# power_phase.net
KiCad netlist of a schematic drawn in Altium Designer
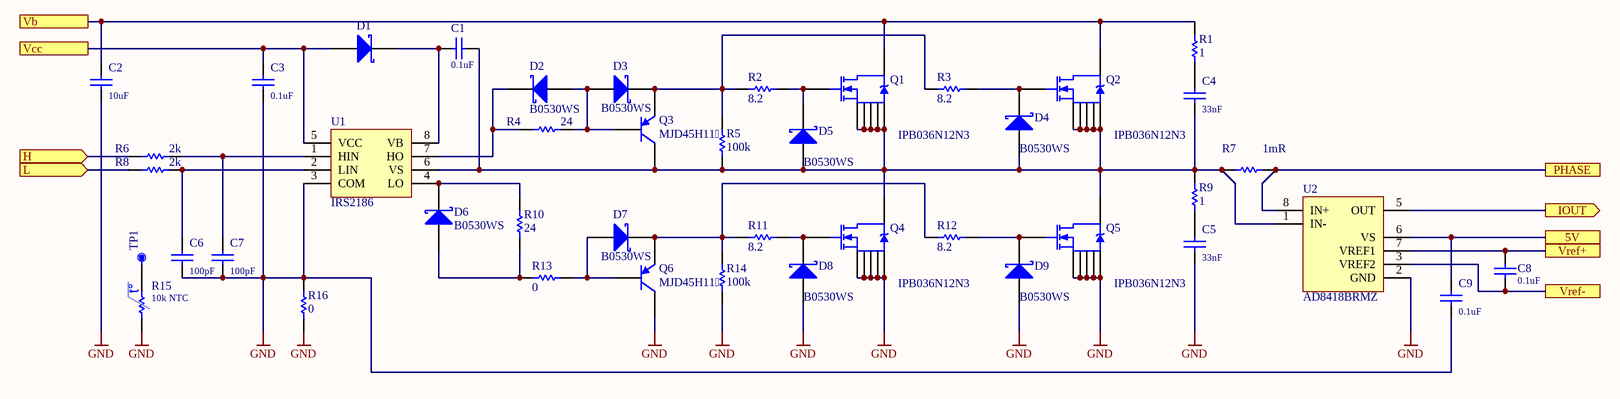
[diagram p0: power_phase.schdoc]

(export (version "E")
  (design (tool "Eeschema 10.0.6"))
  (components
    (comp (ref "C1")
      (value "0.1uF")
      (footprint "C0805_L")
      (description "0.1uF 50V 0603")
      (libsource (lib "Miscellaneous Devices") (part "CAP"))
    )
    (comp (ref "C2")
      (value "10uF")
      (footprint "C2220")
      (description "10uF 100V 2220")
      (libsource (lib "Miscellaneous Devices") (part "CAP"))
    )
    (comp (ref "C3")
      (value "0.1uF")
      (footprint "C0603")
      (description "0.1uF 50V 0603")
      (libsource (lib "Miscellaneous Devices") (part "CAP"))
    )
    (comp (ref "C4")
      (value "33nF")
      (footprint "C0805")
      (description "33nF 100V 1206")
      (libsource (lib "Miscellaneous Devices") (part "CAP"))
    )
    (comp (ref "C5")
      (value "33nF")
      (footprint "C0805")
      (description "33nF 100V 1206")
      (libsource (lib "Miscellaneous Devices") (part "CAP"))
    )
    (comp (ref "C6")
      (value "100pF")
      (footprint "C0402")
      (description "100pF 50V 0402")
      (libsource (lib "Miscellaneous Devices") (part "CAP"))
    )
    (comp (ref "C7")
      (value "100pF")
      (footprint "C0402")
      (description "100pF 50V 0402")
      (libsource (lib "Miscellaneous Devices") (part "CAP"))
    )
    (comp (ref "C8")
      (value "0.1uF")
      (footprint "C0402")
      (description "0.1uF 50V 0603")
      (libsource (lib "Miscellaneous Devices") (part "CAP"))
    )
    (comp (ref "C9")
      (value "0.1uF")
      (footprint "C0402")
      (description "0.1uF 50V 0603")
      (libsource (lib "Miscellaneous Devices") (part "CAP"))
    )
    (comp (ref "D1")
      (value "~")
      (footprint "SOD-323")
      (description "100V SOD-323")
      (libsource (lib "Miscellaneous Devices") (part "Diode 10TQ035_1"))
    )
    (comp (ref "D2")
      (value "B0530WS")
      (footprint "SOD-323")
      (description "Schottky 0.5A 30V SOD-323")
      (libsource (lib "Miscellaneous Devices") (part "Diode 10TQ035_1"))
    )
    (comp (ref "D3")
      (value "B0530WS")
      (footprint "SOD-323")
      (description "Schottky 0.5A 30V SOD-323")
      (libsource (lib "Miscellaneous Devices") (part "Diode 10TQ035_1"))
    )
    (comp (ref "D4")
      (value "B0530WS")
      (footprint "SOD-323")
      (description "Schottky 0.5A 30V SOD-323")
      (libsource (lib "Miscellaneous Devices") (part "Diode 10TQ035_1"))
    )
    (comp (ref "D5")
      (value "B0530WS")
      (footprint "SOD-323")
      (description "Schottky 0.5A 30V SOD-323")
      (libsource (lib "Miscellaneous Devices") (part "Diode 10TQ035_1"))
    )
    (comp (ref "D6")
      (value "B0530WS")
      (footprint "SOD-323")
      (description "Schottky 0.5A 30V SOD-323")
      (libsource (lib "Miscellaneous Devices") (part "Diode 10TQ035_1"))
    )
    (comp (ref "D7")
      (value "B0530WS")
      (footprint "SOD-323")
      (description "Schottky 0.5A 30V SOD-323")
      (libsource (lib "Miscellaneous Devices") (part "Diode 10TQ035_1"))
    )
    (comp (ref "D8")
      (value "B0530WS")
      (footprint "SOD-323")
      (description "Schottky 0.5A 30V SOD-323")
      (libsource (lib "Miscellaneous Devices") (part "Diode 10TQ035_1"))
    )
    (comp (ref "D9")
      (value "B0530WS")
      (footprint "SOD-323")
      (description "Schottky 0.5A 30V SOD-323")
      (libsource (lib "Miscellaneous Devices") (part "Diode 10TQ035_1"))
    )
    (comp (ref "Q1")
      (value "IPB036N12N3")
      (footprint "TO-263-7")
      (description "IPB036N12N3GATMA1")
      (libsource (lib "Miscellaneous Devices") (part "NMOS-2"))
    )
    (comp (ref "Q2")
      (value "IPB036N12N3")
      (footprint "TO-263-7")
      (description "IPB036N12N3GATMA1")
      (libsource (lib "Miscellaneous Devices") (part "NMOS-2"))
    )
    (comp (ref "Q3")
      (value "MJD45H11")
      (footprint "TO-252AA")
      (description "PNP Bipolar Transistor")
      (libsource (lib "Miscellaneous Devices") (part "PNP"))
    )
    (comp (ref "Q4")
      (value "IPB036N12N3")
      (footprint "TO-263-7")
      (description "IPB036N12N3GATMA1")
      (libsource (lib "Miscellaneous Devices") (part "NMOS-2"))
    )
    (comp (ref "Q5")
      (value "IPB036N12N3")
      (footprint "TO-263-7")
      (description "IPB036N12N3GATMA1")
      (libsource (lib "Miscellaneous Devices") (part "NMOS-2"))
    )
    (comp (ref "Q6")
      (value "MJD45H11")
      (footprint "TO-252AA")
      (description "PNP Bipolar Transistor")
      (libsource (lib "Miscellaneous Devices") (part "PNP"))
    )
    (comp (ref "R1")
      (value "1")
      (footprint "R1206")
      (description "1R 5% 1206")
      (libsource (lib "Miscellaneous Devices") (part "Res1"))
    )
    (comp (ref "R2")
      (value "8.2")
      (footprint "R0805")
      (description "8.2R 5% 0805")
      (libsource (lib "Miscellaneous Devices") (part "Res1"))
    )
    (comp (ref "R3")
      (value "8.2")
      (footprint "R0805")
      (description "8.2R 5% 0805")
      (libsource (lib "Miscellaneous Devices") (part "Res1"))
    )
    (comp (ref "R4")
      (value "24")
      (footprint "R0603")
      (description "24R 5% 0603")
      (libsource (lib "Miscellaneous Devices") (part "Res1"))
    )
    (comp (ref "R5")
      (value "100k")
      (footprint "R0805")
      (description "100k 5% 0805")
      (libsource (lib "Miscellaneous Devices") (part "Res1"))
    )
    (comp (ref "R6")
      (value "2k")
      (footprint "R0603")
      (description "2k 5% 0603")
      (libsource (lib "Miscellaneous Devices") (part "Res1"))
    )
    (comp (ref "R7")
      (value "1mR")
      (footprint "RES_CSS2H-3920R")
      (description "1mR 3920R")
      (libsource (lib "Miscellaneous Devices") (part "Res1"))
    )
    (comp (ref "R8")
      (value "2k")
      (footprint "R0603")
      (description "2k 5% 0603")
      (libsource (lib "Miscellaneous Devices") (part "Res1"))
    )
    (comp (ref "R9")
      (value "1")
      (footprint "R1206")
      (description "1R 5% 1206")
      (libsource (lib "Miscellaneous Devices") (part "Res1"))
    )
    (comp (ref "R10")
      (value "24")
      (footprint "R0603")
      (description "24R 5% 0603")
      (libsource (lib "Miscellaneous Devices") (part "Res1"))
    )
    (comp (ref "R11")
      (value "8.2")
      (footprint "R0805")
      (description "8.2R 5% 0805")
      (libsource (lib "Miscellaneous Devices") (part "Res1"))
    )
    (comp (ref "R12")
      (value "8.2")
      (footprint "R0805")
      (description "8.2R 5% 0805")
      (libsource (lib "Miscellaneous Devices") (part "Res1"))
    )
    (comp (ref "R13")
      (value "0")
      (footprint "R1206")
      (description "0 2512")
      (libsource (lib "Miscellaneous Devices") (part "Res1"))
    )
    (comp (ref "R14")
      (value "100k")
      (footprint "R0805")
      (description "100k 5% 0805")
      (libsource (lib "Miscellaneous Devices") (part "Res1"))
    )
    (comp (ref "R15")
      (value "10k NTC")
      (footprint "R0402")
      (description "10k NTC 3434 0402")
      (libsource (lib "Miscellaneous Devices") (part "RES"))
    )
    (comp (ref "R16")
      (value "0")
      (footprint "R1206")
      (description "0 2512")
      (libsource (lib "Miscellaneous Devices") (part "Res1"))
    )
    (comp (ref "TP1")
      (value "~")
      (footprint "TP2030_SMD")
      (libsource (lib "Miscellaneous Devices") (part "TP_Dup1"))
    )
    (comp (ref "U1")
      (value "IRS2186")
      (footprint "SO-8")
      (description "IR2186")
      (libsource (lib "Miscellaneous Devices") (part "IRS2186"))
    )
    (comp (ref "U2")
      (value "AD8418BRMZ")
      (footprint "MSOP8")
      (description "Bidirectional, Zero Drift, Current Sense Amplifier")
      (libsource (lib "schlib") (part "AD8418BRMZ"))
    )
  )
  (nets
    (net (code "1") (name "/5V") (class "Default")
      (node (ref "C9") (pin "2") (pinfunction "2_2") (pintype "passive"))
      (node (ref "U2") (pin "6") (pinfunction "VS_6") (pintype "passive"))
    )
    (net (code "2") (name "/H") (class "Default")
      (node (ref "R6") (pin "2") (pinfunction "2_2") (pintype "passive"))
    )
    (net (code "3") (name "/IOUT") (class "Default")
      (node (ref "U2") (pin "5") (pinfunction "OUT_5") (pintype "passive"))
    )
    (net (code "4") (name "/L") (class "Default")
      (node (ref "R8") (pin "2") (pinfunction "2_2") (pintype "passive"))
    )
    (net (code "5") (name "/PHASE") (class "Default")
      (node (ref "R7") (pin "2") (pinfunction "2_2") (pintype "passive"))
      (node (ref "U2") (pin "8") (pinfunction "IN+_8") (pintype "passive"))
    )
    (net (code "6") (name "/Vb") (class "Default")
      (node (ref "C2") (pin "2") (pinfunction "2_2") (pintype "passive"))
      (node (ref "Q1") (pin "4") (pinfunction "D_4") (pintype "passive"))
      (node (ref "Q2") (pin "4") (pinfunction "D_4") (pintype "passive"))
      (node (ref "R1") (pin "2") (pinfunction "2_2") (pintype "passive"))
    )
    (net (code "7") (name "/Vcc") (class "Default")
      (node (ref "C3") (pin "2") (pinfunction "2_2") (pintype "passive"))
      (node (ref "D1") (pin "1") (pinfunction "A_1") (pintype "passive"))
      (node (ref "U1") (pin "5") (pinfunction "VCC_5") (pintype "power_in"))
    )
    (net (code "8") (name "/Vref+") (class "Default")
      (node (ref "C8") (pin "2") (pinfunction "2_2") (pintype "passive"))
      (node (ref "U2") (pin "7") (pinfunction "VREF1_7") (pintype "passive"))
    )
    (net (code "9") (name "/Vref-") (class "Default")
      (node (ref "C8") (pin "1") (pinfunction "1_1") (pintype "passive"))
      (node (ref "U2") (pin "3") (pinfunction "VREF2_3") (pintype "passive"))
    )
    (net (code "10") (name "GND") (class "Default")
      (node (ref "C2") (pin "1") (pinfunction "1_1") (pintype "passive"))
      (node (ref "C3") (pin "1") (pinfunction "1_1") (pintype "passive"))
      (node (ref "C5") (pin "1") (pinfunction "1_1") (pintype "passive"))
      (node (ref "C6") (pin "1") (pinfunction "1_1") (pintype "passive"))
      (node (ref "C7") (pin "1") (pinfunction "1_1") (pintype "passive"))
      (node (ref "C9") (pin "1") (pinfunction "1_1") (pintype "passive"))
      (node (ref "D8") (pin "1") (pinfunction "A_1") (pintype "passive"))
      (node (ref "D9") (pin "1") (pinfunction "A_1") (pintype "passive"))
      (node (ref "Q4") (pin "2") (pinfunction "S_2") (pintype "passive"))
      (node (ref "Q4") (pin "3") (pinfunction "S_3") (pintype "passive"))
      (node (ref "Q4") (pin "5") (pinfunction "S_5") (pintype "passive"))
      (node (ref "Q4") (pin "6") (pinfunction "S_6") (pintype "passive"))
      (node (ref "Q4") (pin "7") (pinfunction "S_7") (pintype "passive"))
      (node (ref "Q5") (pin "2") (pinfunction "S_2") (pintype "passive"))
      (node (ref "Q5") (pin "3") (pinfunction "S_3") (pintype "passive"))
      (node (ref "Q5") (pin "5") (pinfunction "S_5") (pintype "passive"))
      (node (ref "Q5") (pin "6") (pinfunction "S_6") (pintype "passive"))
      (node (ref "Q5") (pin "7") (pinfunction "S_7") (pintype "passive"))
      (node (ref "Q6") (pin "2") (pinfunction "C_2") (pintype "passive"))
      (node (ref "R14") (pin "2") (pinfunction "2_2") (pintype "passive"))
      (node (ref "R15") (pin "2") (pinfunction "2_2") (pintype "passive"))
      (node (ref "R16") (pin "1") (pinfunction "1_1") (pintype "passive"))
      (node (ref "R16") (pin "2") (pinfunction "2_2") (pintype "passive"))
      (node (ref "U1") (pin "3") (pinfunction "COM_3") (pintype "power_in"))
      (node (ref "U2") (pin "2") (pinfunction "GND_2") (pintype "passive"))
    )
    (net (code "11") (name "Net-(C4-Pad2)") (class "Default")
      (node (ref "C4") (pin "2") (pinfunction "2_2") (pintype "passive"))
      (node (ref "R1") (pin "1") (pinfunction "1_1") (pintype "passive"))
    )
    (net (code "12") (name "Net-(C5-Pad2)") (class "Default")
      (node (ref "C5") (pin "2") (pinfunction "2_2") (pintype "passive"))
      (node (ref "R9") (pin "1") (pinfunction "1_1") (pintype "passive"))
    )
    (net (code "13") (name "Net-(D1-K)") (class "Default")
      (node (ref "C1") (pin "1") (pinfunction "1_1") (pintype "passive"))
      (node (ref "D1") (pin "2") (pinfunction "K_2") (pintype "passive"))
      (node (ref "U1") (pin "8") (pinfunction "VB_8") (pintype "passive"))
    )
    (net (code "14") (name "Net-(D2-A)") (class "Default")
      (node (ref "D2") (pin "1") (pinfunction "A_1") (pintype "passive"))
      (node (ref "D3") (pin "1") (pinfunction "A_1") (pintype "passive"))
      (node (ref "Q3") (pin "1") (pinfunction "B_1") (pintype "passive"))
      (node (ref "R4") (pin "1") (pinfunction "1_1") (pintype "passive"))
    )
    (net (code "15") (name "Net-(D2-K)") (class "Default")
      (node (ref "D2") (pin "2") (pinfunction "K_2") (pintype "passive"))
      (node (ref "R4") (pin "2") (pinfunction "2_2") (pintype "passive"))
      (node (ref "U1") (pin "7") (pinfunction "HO_7") (pintype "passive"))
    )
    (net (code "16") (name "Net-(D3-K)") (class "Default")
      (node (ref "D3") (pin "2") (pinfunction "K_2") (pintype "passive"))
      (node (ref "Q3") (pin "3") (pinfunction "E_3") (pintype "passive"))
      (node (ref "R2") (pin "1") (pinfunction "1_1") (pintype "passive"))
      (node (ref "R3") (pin "1") (pinfunction "1_1") (pintype "passive"))
      (node (ref "R5") (pin "1") (pinfunction "1_1") (pintype "passive"))
    )
    (net (code "17") (name "Net-(D4-A)") (class "Default")
      (node (ref "C1") (pin "2") (pinfunction "2_2") (pintype "passive"))
      (node (ref "C4") (pin "1") (pinfunction "1_1") (pintype "passive"))
      (node (ref "D4") (pin "1") (pinfunction "A_1") (pintype "passive"))
      (node (ref "D5") (pin "1") (pinfunction "A_1") (pintype "passive"))
      (node (ref "Q1") (pin "2") (pinfunction "S_2") (pintype "passive"))
      (node (ref "Q1") (pin "3") (pinfunction "S_3") (pintype "passive"))
      (node (ref "Q1") (pin "5") (pinfunction "S_5") (pintype "passive"))
      (node (ref "Q1") (pin "6") (pinfunction "S_6") (pintype "passive"))
      (node (ref "Q1") (pin "7") (pinfunction "S_7") (pintype "passive"))
      (node (ref "Q2") (pin "2") (pinfunction "S_2") (pintype "passive"))
      (node (ref "Q2") (pin "3") (pinfunction "S_3") (pintype "passive"))
      (node (ref "Q2") (pin "5") (pinfunction "S_5") (pintype "passive"))
      (node (ref "Q2") (pin "6") (pinfunction "S_6") (pintype "passive"))
      (node (ref "Q2") (pin "7") (pinfunction "S_7") (pintype "passive"))
      (node (ref "Q3") (pin "2") (pinfunction "C_2") (pintype "passive"))
      (node (ref "Q4") (pin "4") (pinfunction "D_4") (pintype "passive"))
      (node (ref "Q5") (pin "4") (pinfunction "D_4") (pintype "passive"))
      (node (ref "R5") (pin "2") (pinfunction "2_2") (pintype "passive"))
      (node (ref "R7") (pin "1") (pinfunction "1_1") (pintype "passive"))
      (node (ref "R9") (pin "2") (pinfunction "2_2") (pintype "passive"))
      (node (ref "U1") (pin "6") (pinfunction "VS_6") (pintype "passive"))
      (node (ref "U2") (pin "1") (pinfunction "IN-_1") (pintype "passive"))
    )
    (net (code "18") (name "Net-(D4-K)") (class "Default")
      (node (ref "D4") (pin "2") (pinfunction "K_2") (pintype "passive"))
      (node (ref "Q2") (pin "1") (pinfunction "G_1") (pintype "passive"))
      (node (ref "R3") (pin "2") (pinfunction "2_2") (pintype "passive"))
    )
    (net (code "19") (name "Net-(D5-K)") (class "Default")
      (node (ref "D5") (pin "2") (pinfunction "K_2") (pintype "passive"))
      (node (ref "Q1") (pin "1") (pinfunction "G_1") (pintype "passive"))
      (node (ref "R2") (pin "2") (pinfunction "2_2") (pintype "passive"))
    )
    (net (code "20") (name "Net-(D6-A)") (class "Default")
      (node (ref "D6") (pin "1") (pinfunction "A_1") (pintype "passive"))
      (node (ref "R10") (pin "1") (pinfunction "1_1") (pintype "passive"))
      (node (ref "R13") (pin "2") (pinfunction "2_2") (pintype "passive"))
    )
    (net (code "21") (name "Net-(D6-K)") (class "Default")
      (node (ref "D6") (pin "2") (pinfunction "K_2") (pintype "passive"))
      (node (ref "R10") (pin "2") (pinfunction "2_2") (pintype "passive"))
      (node (ref "U1") (pin "4") (pinfunction "LO_4") (pintype "passive"))
    )
    (net (code "22") (name "Net-(D7-A)") (class "Default")
      (node (ref "D7") (pin "1") (pinfunction "A_1") (pintype "passive"))
      (node (ref "Q6") (pin "1") (pinfunction "B_1") (pintype "passive"))
      (node (ref "R13") (pin "1") (pinfunction "1_1") (pintype "passive"))
    )
    (net (code "23") (name "Net-(D7-K)") (class "Default")
      (node (ref "D7") (pin "2") (pinfunction "K_2") (pintype "passive"))
      (node (ref "Q6") (pin "3") (pinfunction "E_3") (pintype "passive"))
      (node (ref "R11") (pin "1") (pinfunction "1_1") (pintype "passive"))
      (node (ref "R12") (pin "1") (pinfunction "1_1") (pintype "passive"))
      (node (ref "R14") (pin "1") (pinfunction "1_1") (pintype "passive"))
    )
    (net (code "24") (name "Net-(D8-K)") (class "Default")
      (node (ref "D8") (pin "2") (pinfunction "K_2") (pintype "passive"))
      (node (ref "Q4") (pin "1") (pinfunction "G_1") (pintype "passive"))
      (node (ref "R11") (pin "2") (pinfunction "2_2") (pintype "passive"))
    )
    (net (code "25") (name "Net-(D9-K)") (class "Default")
      (node (ref "D9") (pin "2") (pinfunction "K_2") (pintype "passive"))
      (node (ref "Q5") (pin "1") (pinfunction "G_1") (pintype "passive"))
      (node (ref "R12") (pin "2") (pinfunction "2_2") (pintype "passive"))
    )
    (net (code "26") (name "Net-(R15-Pad1)") (class "Default")
      (node (ref "R15") (pin "1") (pinfunction "1_1") (pintype "passive"))
      (node (ref "TP1") (pin "1") (pinfunction "1_1") (pintype "passive"))
    )
    (net (code "27") (name "Net-(U1-HIN)") (class "Default")
      (node (ref "C7") (pin "2") (pinfunction "2_2") (pintype "passive"))
      (node (ref "R6") (pin "1") (pinfunction "1_1") (pintype "passive"))
      (node (ref "U1") (pin "1") (pinfunction "HIN_1") (pintype "passive"))
    )
    (net (code "28") (name "Net-(U1-LIN)") (class "Default")
      (node (ref "C6") (pin "2") (pinfunction "2_2") (pintype "passive"))
      (node (ref "R8") (pin "1") (pinfunction "1_1") (pintype "passive"))
      (node (ref "U1") (pin "2") (pinfunction "LIN_2") (pintype "passive"))
    )
  )
)
